# h-bridge_mosfets_ver_4.net
KiCad netlist of a schematic drawn in EAGLE
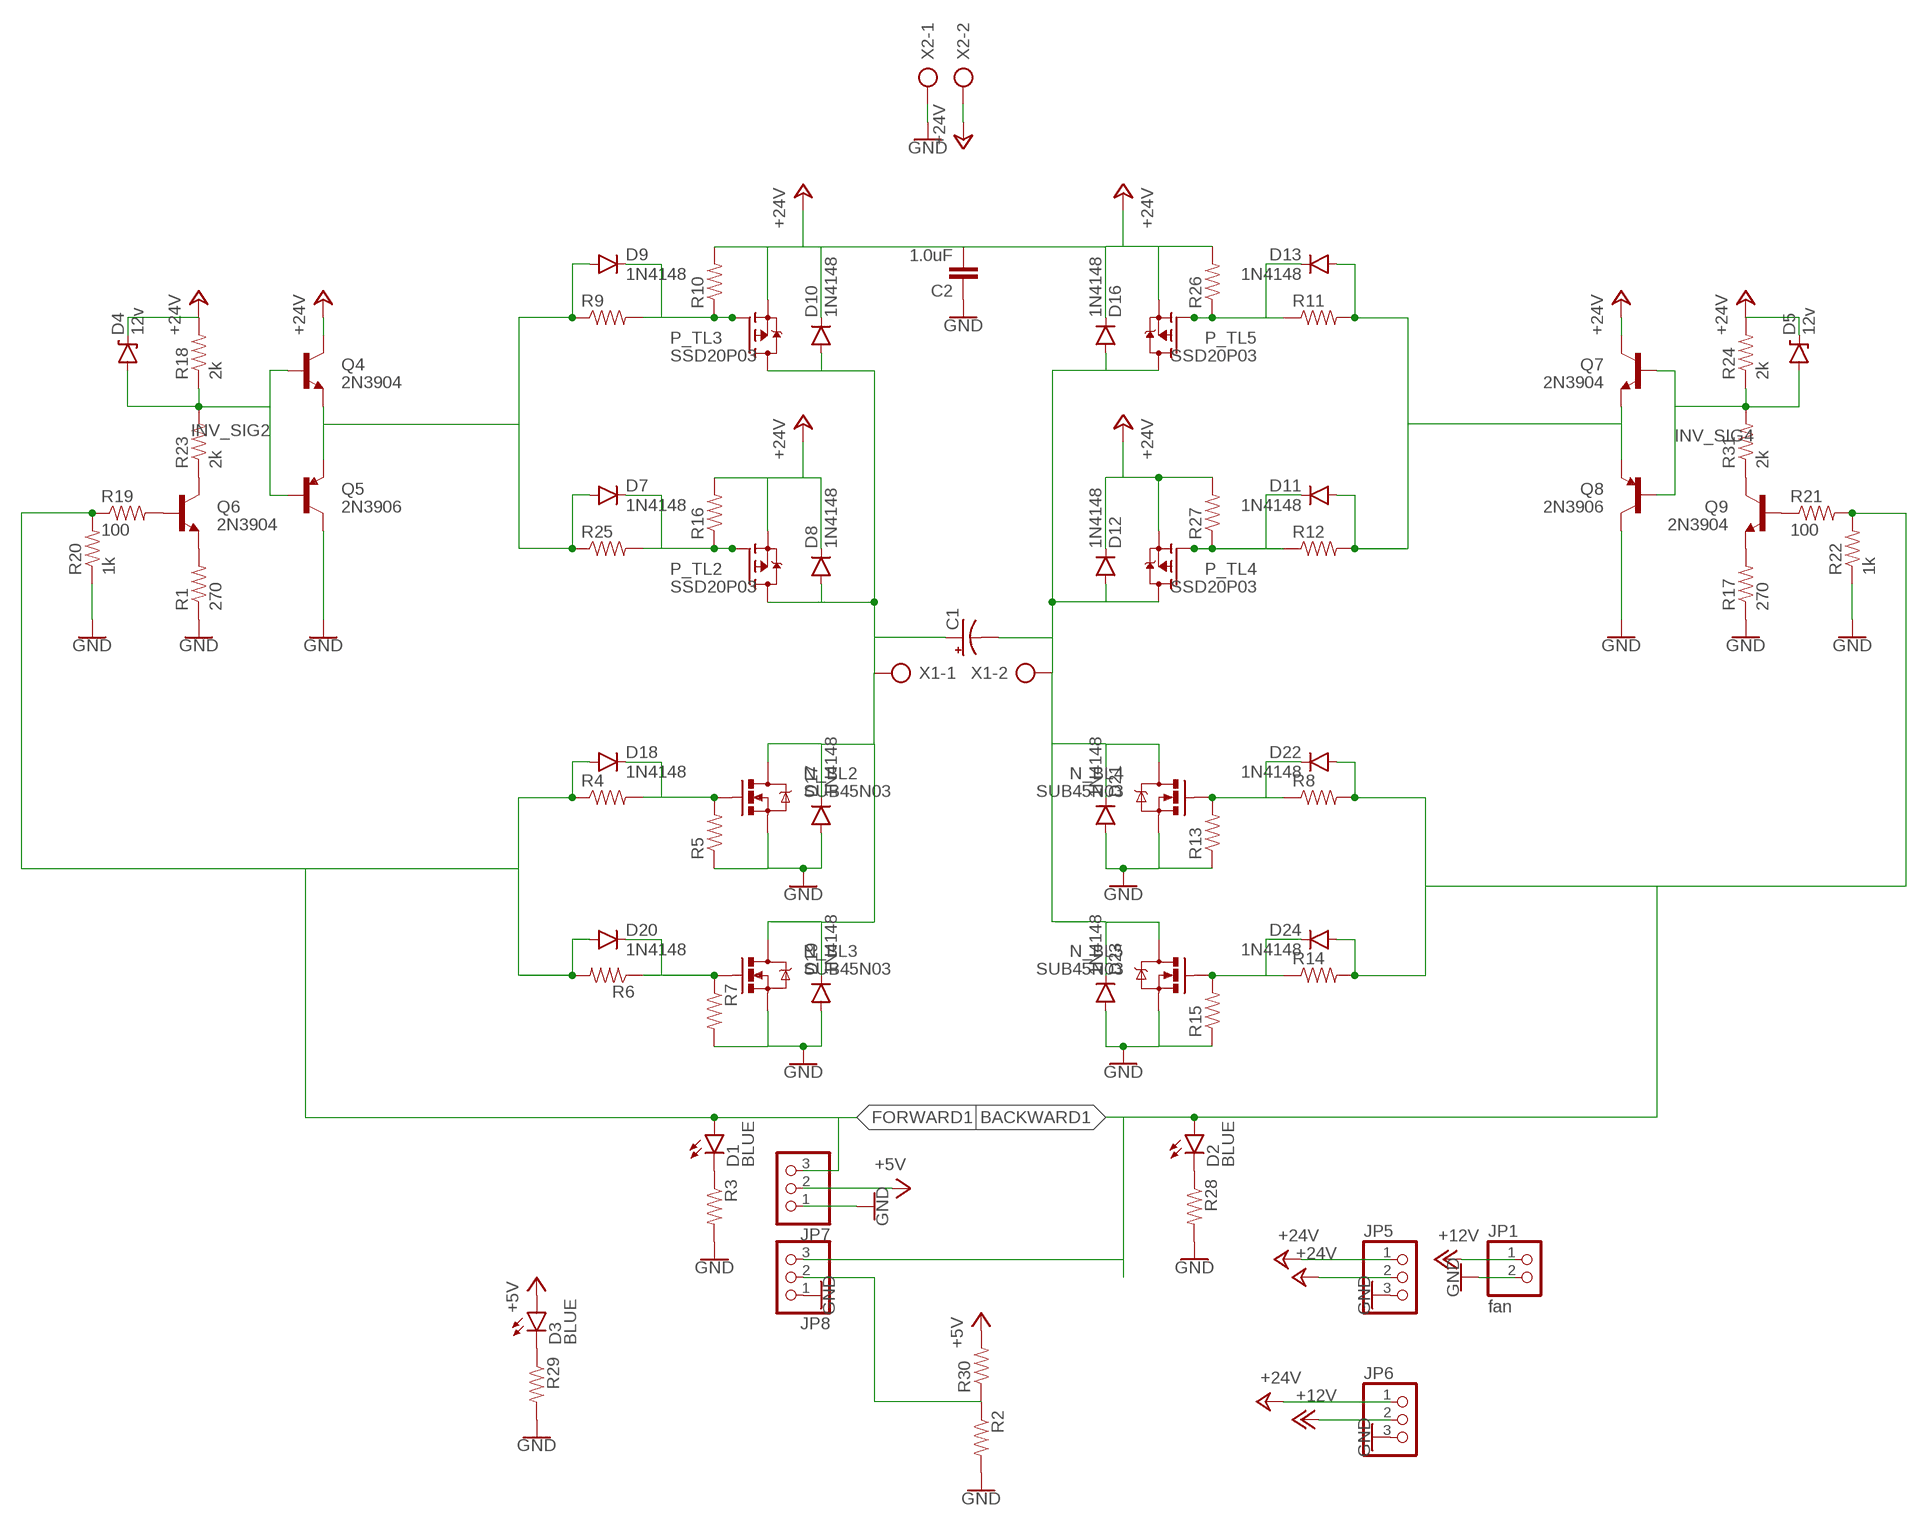
[diagram p0: schematic, sheet 1]

(export (version "E")
  (design (tool "Eeschema 10.0.6"))
  (components
    (comp (ref "C1")
      (value "1000UF-25V(PTH)")
      (footprint "eagle-import:CPOL-RADIAL-1000UF-25V")
      (libsource (lib "eagle-import") (part "1000UF-25V(PTH)"))
    )
    (comp (ref "C2")
      (value "1.0uF")
      (footprint "eagle-import:1206")
      (libsource (lib "eagle-import") (part "1.0UF50V10%(1206)"))
    )
    (comp (ref "D1")
      (value "BLUE")
      (footprint "eagle-import:LED-1206")
      (libsource (lib "eagle-import") (part "LED-BLUE1206"))
    )
    (comp (ref "D2")
      (value "BLUE")
      (footprint "eagle-import:LED-1206")
      (libsource (lib "eagle-import") (part "LED-BLUE1206"))
    )
    (comp (ref "D3")
      (value "BLUE")
      (footprint "eagle-import:LED-1206")
      (libsource (lib "eagle-import") (part "LED-BLUE1206"))
    )
    (comp (ref "D4")
      (value "12v")
      (footprint "eagle-import:SMB-DIODE")
      (libsource (lib "eagle-import") (part "DIODE-ZENERSMB"))
    )
    (comp (ref "D5")
      (value "12v")
      (footprint "eagle-import:SMB-DIODE")
      (libsource (lib "eagle-import") (part "DIODE-ZENERSMB"))
    )
    (comp (ref "D7")
      (value "1N4148")
      (footprint "eagle-import:SOD-123")
      (libsource (lib "eagle-import") (part "DIODESOD123"))
    )
    (comp (ref "D8")
      (value "1N4148")
      (footprint "eagle-import:SOD-123")
      (libsource (lib "eagle-import") (part "DIODESOD123"))
    )
    (comp (ref "D9")
      (value "1N4148")
      (footprint "eagle-import:SOD-123")
      (libsource (lib "eagle-import") (part "DIODESOD123"))
    )
    (comp (ref "D10")
      (value "1N4148")
      (footprint "eagle-import:SOD-123")
      (libsource (lib "eagle-import") (part "DIODESOD123"))
    )
    (comp (ref "D11")
      (value "1N4148")
      (footprint "eagle-import:SOD-123")
      (libsource (lib "eagle-import") (part "DIODESOD123"))
    )
    (comp (ref "D12")
      (value "1N4148")
      (footprint "eagle-import:SOD-123")
      (libsource (lib "eagle-import") (part "DIODESOD123"))
    )
    (comp (ref "D13")
      (value "1N4148")
      (footprint "eagle-import:SOD-123")
      (libsource (lib "eagle-import") (part "DIODESOD123"))
    )
    (comp (ref "D16")
      (value "1N4148")
      (footprint "eagle-import:SOD-123")
      (libsource (lib "eagle-import") (part "DIODESOD123"))
    )
    (comp (ref "D17")
      (value "1N4148")
      (footprint "eagle-import:SOD-123")
      (libsource (lib "eagle-import") (part "DIODESOD123"))
    )
    (comp (ref "D18")
      (value "1N4148")
      (footprint "eagle-import:SOD-123")
      (libsource (lib "eagle-import") (part "DIODESOD123"))
    )
    (comp (ref "D19")
      (value "1N4148")
      (footprint "eagle-import:SOD-123")
      (libsource (lib "eagle-import") (part "DIODESOD123"))
    )
    (comp (ref "D20")
      (value "1N4148")
      (footprint "eagle-import:SOD-123")
      (libsource (lib "eagle-import") (part "DIODESOD123"))
    )
    (comp (ref "D21")
      (value "1N4148")
      (footprint "eagle-import:SOD-123")
      (libsource (lib "eagle-import") (part "DIODESOD123"))
    )
    (comp (ref "D22")
      (value "1N4148")
      (footprint "eagle-import:SOD-123")
      (libsource (lib "eagle-import") (part "DIODESOD123"))
    )
    (comp (ref "D23")
      (value "1N4148")
      (footprint "eagle-import:SOD-123")
      (libsource (lib "eagle-import") (part "DIODESOD123"))
    )
    (comp (ref "D24")
      (value "1N4148")
      (footprint "eagle-import:SOD-123")
      (libsource (lib "eagle-import") (part "DIODESOD123"))
    )
    (comp (ref "JP1")
      (value "fan")
      (footprint "eagle-import:1X02")
      (libsource (lib "eagle-import") (part "PINHD-1X2"))
    )
    (comp (ref "JP5")
      (value "PINHD-1X3")
      (footprint "eagle-import:1X03")
      (libsource (lib "eagle-import") (part "PINHD-1X3"))
    )
    (comp (ref "JP6")
      (value "PINHD-1X3")
      (footprint "eagle-import:1X03")
      (libsource (lib "eagle-import") (part "PINHD-1X3"))
    )
    (comp (ref "JP7")
      (value "PINHD-1X3")
      (footprint "eagle-import:1X03")
      (libsource (lib "eagle-import") (part "PINHD-1X3"))
    )
    (comp (ref "JP8")
      (value "PINHD-1X3")
      (footprint "eagle-import:1X03")
      (libsource (lib "eagle-import") (part "PINHD-1X3"))
    )
    (comp (ref "N_BL2")
      (value "SUB45N03")
      (footprint "eagle-import:TO-263_D2PAK")
      (libsource (lib "eagle-import") (part "MOSFET-NCHANNELPSMN7R0"))
    )
    (comp (ref "N_BL3")
      (value "SUB45N03")
      (footprint "eagle-import:TO-263_D2PAK")
      (libsource (lib "eagle-import") (part "MOSFET-NCHANNELPSMN7R0"))
    )
    (comp (ref "N_BL4")
      (value "SUB45N03")
      (footprint "eagle-import:TO-263_D2PAK")
      (libsource (lib "eagle-import") (part "MOSFET-NCHANNELPSMN7R0"))
    )
    (comp (ref "N_BL5")
      (value "SUB45N03")
      (footprint "eagle-import:TO-263_D2PAK")
      (libsource (lib "eagle-import") (part "MOSFET-NCHANNELPSMN7R0"))
    )
    (comp (ref "P_TL2")
      (value "SSD20P03")
      (footprint "eagle-import:TO252")
      (libsource (lib "eagle-import") (part "FDD4141TO252"))
    )
    (comp (ref "P_TL3")
      (value "SSD20P03")
      (footprint "eagle-import:TO252")
      (libsource (lib "eagle-import") (part "FDD4141TO252"))
    )
    (comp (ref "P_TL4")
      (value "SSD20P03")
      (footprint "eagle-import:TO252")
      (libsource (lib "eagle-import") (part "FDD4141TO252"))
    )
    (comp (ref "P_TL5")
      (value "SSD20P03")
      (footprint "eagle-import:TO252")
      (libsource (lib "eagle-import") (part "FDD4141TO252"))
    )
    (comp (ref "Q4")
      (value "2N3904")
      (footprint "eagle-import:SOT23-3")
      (libsource (lib "eagle-import") (part "TRANSISTOR_NPNMMBT5088"))
    )
    (comp (ref "Q5")
      (value "2N3906")
      (footprint "eagle-import:SOT23-3")
      (libsource (lib "eagle-import") (part "TRANSISTOR_PNPPMBT3906"))
    )
    (comp (ref "Q6")
      (value "2N3904")
      (footprint "eagle-import:SOT23-3")
      (libsource (lib "eagle-import") (part "TRANSISTOR_NPNMMBT5088"))
    )
    (comp (ref "Q7")
      (value "2N3904")
      (footprint "eagle-import:SOT23-3")
      (libsource (lib "eagle-import") (part "TRANSISTOR_NPNMMBT5088"))
    )
    (comp (ref "Q8")
      (value "2N3906")
      (footprint "eagle-import:SOT23-3")
      (libsource (lib "eagle-import") (part "TRANSISTOR_PNPPMBT3906"))
    )
    (comp (ref "Q9")
      (value "2N3904")
      (footprint "eagle-import:SOT23-3")
      (libsource (lib "eagle-import") (part "TRANSISTOR_NPNMMBT5088"))
    )
    (comp (ref "R1")
      (value "270")
      (footprint "eagle-import:0805")
      (libsource (lib "eagle-import") (part "0.3OHM-1/8W-1%(0805)"))
    )
    (comp (ref "R2")
      (value "0.3OHM-1/8W-1%(0805)")
      (footprint "eagle-import:0805")
      (libsource (lib "eagle-import") (part "0.3OHM-1/8W-1%(0805)"))
    )
    (comp (ref "R3")
      (value "0.3OHM-1/8W-1%(0805)")
      (footprint "eagle-import:0805")
      (libsource (lib "eagle-import") (part "0.3OHM-1/8W-1%(0805)"))
    )
    (comp (ref "R4")
      (value "0.3OHM-1/8W-1%(0805)")
      (footprint "eagle-import:0805")
      (libsource (lib "eagle-import") (part "0.3OHM-1/8W-1%(0805)"))
    )
    (comp (ref "R5")
      (value "0.3OHM-1/8W-1%(0805)")
      (footprint "eagle-import:0805")
      (libsource (lib "eagle-import") (part "0.3OHM-1/8W-1%(0805)"))
    )
    (comp (ref "R6")
      (value "0.3OHM-1/8W-1%(0805)")
      (footprint "eagle-import:0805")
      (libsource (lib "eagle-import") (part "0.3OHM-1/8W-1%(0805)"))
    )
    (comp (ref "R7")
      (value "0.3OHM-1/8W-1%(0805)")
      (footprint "eagle-import:0805")
      (libsource (lib "eagle-import") (part "0.3OHM-1/8W-1%(0805)"))
    )
    (comp (ref "R8")
      (value "0.3OHM-1/8W-1%(0805)")
      (footprint "eagle-import:0805")
      (libsource (lib "eagle-import") (part "0.3OHM-1/8W-1%(0805)"))
    )
    (comp (ref "R9")
      (value "0.3OHM-1/8W-1%(0805)")
      (footprint "eagle-import:0805")
      (libsource (lib "eagle-import") (part "0.3OHM-1/8W-1%(0805)"))
    )
    (comp (ref "R10")
      (value "0.3OHM-1/8W-1%(0805)")
      (footprint "eagle-import:0805")
      (libsource (lib "eagle-import") (part "0.3OHM-1/8W-1%(0805)"))
    )
    (comp (ref "R11")
      (value "0.3OHM-1/8W-1%(0805)")
      (footprint "eagle-import:0805")
      (libsource (lib "eagle-import") (part "0.3OHM-1/8W-1%(0805)"))
    )
    (comp (ref "R12")
      (value "0.3OHM-1/8W-1%(0805)")
      (footprint "eagle-import:0805")
      (libsource (lib "eagle-import") (part "0.3OHM-1/8W-1%(0805)"))
    )
    (comp (ref "R13")
      (value "0.3OHM-1/8W-1%(0805)")
      (footprint "eagle-import:0805")
      (libsource (lib "eagle-import") (part "0.3OHM-1/8W-1%(0805)"))
    )
    (comp (ref "R14")
      (value "0.3OHM-1/8W-1%(0805)")
      (footprint "eagle-import:0805")
      (libsource (lib "eagle-import") (part "0.3OHM-1/8W-1%(0805)"))
    )
    (comp (ref "R15")
      (value "0.3OHM-1/8W-1%(0805)")
      (footprint "eagle-import:0805")
      (libsource (lib "eagle-import") (part "0.3OHM-1/8W-1%(0805)"))
    )
    (comp (ref "R16")
      (value "0.3OHM-1/8W-1%(0805)")
      (footprint "eagle-import:0805")
      (libsource (lib "eagle-import") (part "0.3OHM-1/8W-1%(0805)"))
    )
    (comp (ref "R17")
      (value "270")
      (footprint "eagle-import:0805")
      (libsource (lib "eagle-import") (part "0.3OHM-1/8W-1%(0805)"))
    )
    (comp (ref "R18")
      (value "2k")
      (footprint "eagle-import:0805")
      (libsource (lib "eagle-import") (part "0.3OHM-1/8W-1%(0805)"))
    )
    (comp (ref "R19")
      (value "100")
      (footprint "eagle-import:0805")
      (libsource (lib "eagle-import") (part "0.3OHM-1/8W-1%(0805)"))
    )
    (comp (ref "R20")
      (value "1k")
      (footprint "eagle-import:0805")
      (libsource (lib "eagle-import") (part "0.3OHM-1/8W-1%(0805)"))
    )
    (comp (ref "R21")
      (value "100")
      (footprint "eagle-import:0805")
      (libsource (lib "eagle-import") (part "0.3OHM-1/8W-1%(0805)"))
    )
    (comp (ref "R22")
      (value "1k")
      (footprint "eagle-import:0805")
      (libsource (lib "eagle-import") (part "0.3OHM-1/8W-1%(0805)"))
    )
    (comp (ref "R23")
      (value "2k")
      (footprint "eagle-import:0805")
      (libsource (lib "eagle-import") (part "0.3OHM-1/8W-1%(0805)"))
    )
    (comp (ref "R24")
      (value "2k")
      (footprint "eagle-import:0805")
      (libsource (lib "eagle-import") (part "0.3OHM-1/8W-1%(0805)"))
    )
    (comp (ref "R25")
      (value "0.3OHM-1/8W-1%(0805)")
      (footprint "eagle-import:0805")
      (libsource (lib "eagle-import") (part "0.3OHM-1/8W-1%(0805)"))
    )
    (comp (ref "R26")
      (value "0.3OHM-1/8W-1%(0805)")
      (footprint "eagle-import:0805")
      (libsource (lib "eagle-import") (part "0.3OHM-1/8W-1%(0805)"))
    )
    (comp (ref "R27")
      (value "0.3OHM-1/8W-1%(0805)")
      (footprint "eagle-import:0805")
      (libsource (lib "eagle-import") (part "0.3OHM-1/8W-1%(0805)"))
    )
    (comp (ref "R28")
      (value "0.3OHM-1/8W-1%(0805)")
      (footprint "eagle-import:0805")
      (libsource (lib "eagle-import") (part "0.3OHM-1/8W-1%(0805)"))
    )
    (comp (ref "R29")
      (value "0.3OHM-1/8W-1%(0805)")
      (footprint "eagle-import:0805")
      (libsource (lib "eagle-import") (part "0.3OHM-1/8W-1%(0805)"))
    )
    (comp (ref "R30")
      (value "RESISTORPTH-1/4W-VERT-KIT")
      (footprint "eagle-import:AXIAL-0.1EZ")
      (libsource (lib "eagle-import") (part "RESISTORPTH-1/4W-VERT-KIT"))
    )
    (comp (ref "R31")
      (value "2k")
      (footprint "eagle-import:0805")
      (libsource (lib "eagle-import") (part "0.3OHM-1/8W-1%(0805)"))
    )
    (comp (ref "X1")
      (value "AK300/2")
      (footprint "eagle-import:AK300_2")
      (libsource (lib "eagle-import") (part "AK300/2"))
    )
    (comp (ref "X2")
      (value "AK300/2")
      (footprint "eagle-import:AK300_2")
      (libsource (lib "eagle-import") (part "AK300/2"))
    )
  )
  (nets
    (net (code "1") (name "+5V") (class "Default")
      (node (ref "D3") (pin "A") (pinfunction "A_A") (pintype "passive"))
      (node (ref "JP7") (pin "2") (pinfunction "2_2") (pintype "passive"))
      (node (ref "R30") (pin "P$2") (pinfunction "2_P$2") (pintype "passive"))
    )
    (net (code "2") (name "+12V") (class "Default")
      (node (ref "JP1") (pin "1") (pinfunction "1_1") (pintype "passive"))
      (node (ref "JP6") (pin "2") (pinfunction "2_2") (pintype "passive"))
    )
    (net (code "3") (name "+24V") (class "Default")
      (node (ref "C2") (pin "2") (pinfunction "2_2") (pintype "passive"))
      (node (ref "D10") (pin "C") (pinfunction "C_C") (pintype "passive"))
      (node (ref "D12") (pin "C") (pinfunction "C_C") (pintype "passive"))
      (node (ref "D16") (pin "C") (pinfunction "C_C") (pintype "passive"))
      (node (ref "D4") (pin "C") (pinfunction "C_C") (pintype "passive"))
      (node (ref "D5") (pin "C") (pinfunction "C_C") (pintype "passive"))
      (node (ref "D8") (pin "C") (pinfunction "C_C") (pintype "passive"))
      (node (ref "JP5") (pin "1") (pinfunction "1_1") (pintype "passive"))
      (node (ref "JP5") (pin "2") (pinfunction "2_2") (pintype "passive"))
      (node (ref "JP6") (pin "1") (pinfunction "1_1") (pintype "passive"))
      (node (ref "P_TL2") (pin "2") (pinfunction "S_2") (pintype "passive"))
      (node (ref "P_TL3") (pin "2") (pinfunction "S_2") (pintype "passive"))
      (node (ref "P_TL4") (pin "2") (pinfunction "S_2") (pintype "passive"))
      (node (ref "P_TL5") (pin "2") (pinfunction "S_2") (pintype "passive"))
      (node (ref "Q4") (pin "3") (pinfunction "C_3") (pintype "passive"))
      (node (ref "Q7") (pin "3") (pinfunction "C_3") (pintype "passive"))
      (node (ref "R10") (pin "2") (pinfunction "2_2") (pintype "passive"))
      (node (ref "R16") (pin "2") (pinfunction "2_2") (pintype "passive"))
      (node (ref "R18") (pin "2") (pinfunction "2_2") (pintype "passive"))
      (node (ref "R24") (pin "2") (pinfunction "2_2") (pintype "passive"))
      (node (ref "R26") (pin "2") (pinfunction "2_2") (pintype "passive"))
      (node (ref "R27") (pin "2") (pinfunction "2_2") (pintype "passive"))
      (node (ref "X2") (pin "2") (pinfunction "KL_2") (pintype "passive"))
    )
    (net (code "4") (name "/INV_SIG2") (class "Default")
      (node (ref "D4") (pin "A") (pinfunction "A_A") (pintype "passive"))
      (node (ref "Q4") (pin "1") (pinfunction "B_1") (pintype "passive"))
      (node (ref "Q5") (pin "1") (pinfunction "B_1") (pintype "passive"))
      (node (ref "R18") (pin "1") (pinfunction "1_1") (pintype "passive"))
      (node (ref "R23") (pin "2") (pinfunction "2_2") (pintype "passive"))
    )
    (net (code "5") (name "/INV_SIG4") (class "Default")
      (node (ref "D5") (pin "A") (pinfunction "A_A") (pintype "passive"))
      (node (ref "Q7") (pin "1") (pinfunction "B_1") (pintype "passive"))
      (node (ref "Q8") (pin "1") (pinfunction "B_1") (pintype "passive"))
      (node (ref "R24") (pin "1") (pinfunction "1_1") (pintype "passive"))
      (node (ref "R31") (pin "2") (pinfunction "2_2") (pintype "passive"))
    )
    (net (code "6") (name "BACKWARD1") (class "Default")
      (node (ref "D2") (pin "A") (pinfunction "A_A") (pintype "passive"))
      (node (ref "D22") (pin "A") (pinfunction "A_A") (pintype "passive"))
      (node (ref "D24") (pin "A") (pinfunction "A_A") (pintype "passive"))
      (node (ref "JP8") (pin "3") (pinfunction "3_3") (pintype "passive"))
      (node (ref "R14") (pin "2") (pinfunction "2_2") (pintype "passive"))
      (node (ref "R21") (pin "2") (pinfunction "2_2") (pintype "passive"))
      (node (ref "R22") (pin "2") (pinfunction "2_2") (pintype "passive"))
      (node (ref "R8") (pin "2") (pinfunction "2_2") (pintype "passive"))
    )
    (net (code "7") (name "FORWARD1") (class "Default")
      (node (ref "D1") (pin "A") (pinfunction "A_A") (pintype "passive"))
      (node (ref "D18") (pin "A") (pinfunction "A_A") (pintype "passive"))
      (node (ref "D20") (pin "A") (pinfunction "A_A") (pintype "passive"))
      (node (ref "JP7") (pin "3") (pinfunction "3_3") (pintype "passive"))
      (node (ref "R19") (pin "1") (pinfunction "1_1") (pintype "passive"))
      (node (ref "R20") (pin "2") (pinfunction "2_2") (pintype "passive"))
      (node (ref "R4") (pin "1") (pinfunction "1_1") (pintype "passive"))
      (node (ref "R6") (pin "2") (pinfunction "2_2") (pintype "passive"))
    )
    (net (code "8") (name "GND") (class "Default")
      (node (ref "C2") (pin "1") (pinfunction "1_1") (pintype "passive"))
      (node (ref "D17") (pin "A") (pinfunction "A_A") (pintype "passive"))
      (node (ref "D19") (pin "A") (pinfunction "A_A") (pintype "passive"))
      (node (ref "D21") (pin "A") (pinfunction "A_A") (pintype "passive"))
      (node (ref "D23") (pin "A") (pinfunction "A_A") (pintype "passive"))
      (node (ref "JP1") (pin "2") (pinfunction "2_2") (pintype "passive"))
      (node (ref "JP5") (pin "3") (pinfunction "3_3") (pintype "passive"))
      (node (ref "JP6") (pin "3") (pinfunction "3_3") (pintype "passive"))
      (node (ref "JP7") (pin "1") (pinfunction "1_1") (pintype "passive"))
      (node (ref "JP8") (pin "1") (pinfunction "1_1") (pintype "passive"))
      (node (ref "N_BL2") (pin "3") (pinfunction "S_3") (pintype "passive"))
      (node (ref "N_BL3") (pin "3") (pinfunction "S_3") (pintype "passive"))
      (node (ref "N_BL4") (pin "3") (pinfunction "S_3") (pintype "passive"))
      (node (ref "N_BL5") (pin "3") (pinfunction "S_3") (pintype "passive"))
      (node (ref "Q5") (pin "3") (pinfunction "C_3") (pintype "passive"))
      (node (ref "Q8") (pin "3") (pinfunction "C_3") (pintype "passive"))
      (node (ref "R1") (pin "1") (pinfunction "1_1") (pintype "passive"))
      (node (ref "R13") (pin "1") (pinfunction "1_1") (pintype "passive"))
      (node (ref "R15") (pin "1") (pinfunction "1_1") (pintype "passive"))
      (node (ref "R17") (pin "1") (pinfunction "1_1") (pintype "passive"))
      (node (ref "R2") (pin "2") (pinfunction "2_2") (pintype "passive"))
      (node (ref "R20") (pin "1") (pinfunction "1_1") (pintype "passive"))
      (node (ref "R22") (pin "1") (pinfunction "1_1") (pintype "passive"))
      (node (ref "R28") (pin "2") (pinfunction "2_2") (pintype "passive"))
      (node (ref "R29") (pin "2") (pinfunction "2_2") (pintype "passive"))
      (node (ref "R3") (pin "2") (pinfunction "2_2") (pintype "passive"))
      (node (ref "R5") (pin "1") (pinfunction "1_1") (pintype "passive"))
      (node (ref "R7") (pin "2") (pinfunction "2_2") (pintype "passive"))
      (node (ref "X2") (pin "1") (pinfunction "KL_1") (pintype "passive"))
    )
    (net (code "9") (name "Net-(D1-PadC)") (class "Default")
      (node (ref "D1") (pin "C") (pinfunction "C_C") (pintype "passive"))
      (node (ref "R3") (pin "1") (pinfunction "1_1") (pintype "passive"))
    )
    (net (code "10") (name "Net-(D2-PadC)") (class "Default")
      (node (ref "D2") (pin "C") (pinfunction "C_C") (pintype "passive"))
      (node (ref "R28") (pin "1") (pinfunction "1_1") (pintype "passive"))
    )
    (net (code "11") (name "Net-(D3-PadC)") (class "Default")
      (node (ref "D3") (pin "C") (pinfunction "C_C") (pintype "passive"))
      (node (ref "R29") (pin "1") (pinfunction "1_1") (pintype "passive"))
    )
    (net (code "12") (name "Net-(N_BL2-D)") (class "Default")
      (node (ref "C1") (pin "+") (pinfunction "+_+") (pintype "passive"))
      (node (ref "D10") (pin "A") (pinfunction "A_A") (pintype "passive"))
      (node (ref "D17") (pin "C") (pinfunction "C_C") (pintype "passive"))
      (node (ref "D19") (pin "C") (pinfunction "C_C") (pintype "passive"))
      (node (ref "D8") (pin "A") (pinfunction "A_A") (pintype "passive"))
      (node (ref "N_BL2") (pin "2") (pinfunction "D_2") (pintype "passive"))
      (node (ref "N_BL3") (pin "2") (pinfunction "D_2") (pintype "passive"))
      (node (ref "P_TL2") (pin "3") (pinfunction "D_3") (pintype "passive"))
      (node (ref "P_TL3") (pin "3") (pinfunction "D_3") (pintype "passive"))
      (node (ref "X1") (pin "1") (pinfunction "KL_1") (pintype "passive"))
    )
    (net (code "13") (name "Net-(N_BL2-G)") (class "Default")
      (node (ref "D18") (pin "C") (pinfunction "C_C") (pintype "passive"))
      (node (ref "N_BL2") (pin "1") (pinfunction "G_1") (pintype "passive"))
      (node (ref "R4") (pin "2") (pinfunction "2_2") (pintype "passive"))
      (node (ref "R5") (pin "2") (pinfunction "2_2") (pintype "passive"))
    )
    (net (code "14") (name "Net-(N_BL3-G)") (class "Default")
      (node (ref "D20") (pin "C") (pinfunction "C_C") (pintype "passive"))
      (node (ref "N_BL3") (pin "1") (pinfunction "G_1") (pintype "passive"))
      (node (ref "R6") (pin "1") (pinfunction "1_1") (pintype "passive"))
      (node (ref "R7") (pin "1") (pinfunction "1_1") (pintype "passive"))
    )
    (net (code "15") (name "Net-(N_BL4-D)") (class "Default")
      (node (ref "C1") (pin "-") (pinfunction "-_-") (pintype "passive"))
      (node (ref "D12") (pin "A") (pinfunction "A_A") (pintype "passive"))
      (node (ref "D16") (pin "A") (pinfunction "A_A") (pintype "passive"))
      (node (ref "D21") (pin "C") (pinfunction "C_C") (pintype "passive"))
      (node (ref "D23") (pin "C") (pinfunction "C_C") (pintype "passive"))
      (node (ref "N_BL4") (pin "2") (pinfunction "D_2") (pintype "passive"))
      (node (ref "N_BL5") (pin "2") (pinfunction "D_2") (pintype "passive"))
      (node (ref "P_TL4") (pin "3") (pinfunction "D_3") (pintype "passive"))
      (node (ref "P_TL5") (pin "3") (pinfunction "D_3") (pintype "passive"))
      (node (ref "X1") (pin "2") (pinfunction "KL_2") (pintype "passive"))
    )
    (net (code "16") (name "Net-(N_BL4-G)") (class "Default")
      (node (ref "D22") (pin "C") (pinfunction "C_C") (pintype "passive"))
      (node (ref "N_BL4") (pin "1") (pinfunction "G_1") (pintype "passive"))
      (node (ref "R13") (pin "2") (pinfunction "2_2") (pintype "passive"))
      (node (ref "R8") (pin "1") (pinfunction "1_1") (pintype "passive"))
    )
    (net (code "17") (name "Net-(N_BL5-G)") (class "Default")
      (node (ref "D24") (pin "C") (pinfunction "C_C") (pintype "passive"))
      (node (ref "N_BL5") (pin "1") (pinfunction "G_1") (pintype "passive"))
      (node (ref "R14") (pin "1") (pinfunction "1_1") (pintype "passive"))
      (node (ref "R15") (pin "2") (pinfunction "2_2") (pintype "passive"))
    )
    (net (code "18") (name "Net-(P_TL2-G)") (class "Default")
      (node (ref "D7") (pin "C") (pinfunction "C_C") (pintype "passive"))
      (node (ref "P_TL2") (pin "1") (pinfunction "G_1") (pintype "passive"))
      (node (ref "R16") (pin "1") (pinfunction "1_1") (pintype "passive"))
      (node (ref "R25") (pin "2") (pinfunction "2_2") (pintype "passive"))
    )
    (net (code "19") (name "Net-(P_TL3-G)") (class "Default")
      (node (ref "D9") (pin "C") (pinfunction "C_C") (pintype "passive"))
      (node (ref "P_TL3") (pin "1") (pinfunction "G_1") (pintype "passive"))
      (node (ref "R10") (pin "1") (pinfunction "1_1") (pintype "passive"))
      (node (ref "R9") (pin "2") (pinfunction "2_2") (pintype "passive"))
    )
    (net (code "20") (name "Net-(P_TL4-G)") (class "Default")
      (node (ref "D11") (pin "C") (pinfunction "C_C") (pintype "passive"))
      (node (ref "P_TL4") (pin "1") (pinfunction "G_1") (pintype "passive"))
      (node (ref "R12") (pin "1") (pinfunction "1_1") (pintype "passive"))
      (node (ref "R27") (pin "1") (pinfunction "1_1") (pintype "passive"))
    )
    (net (code "21") (name "Net-(P_TL5-G)") (class "Default")
      (node (ref "D13") (pin "C") (pinfunction "C_C") (pintype "passive"))
      (node (ref "P_TL5") (pin "1") (pinfunction "G_1") (pintype "passive"))
      (node (ref "R11") (pin "1") (pinfunction "1_1") (pintype "passive"))
      (node (ref "R26") (pin "1") (pinfunction "1_1") (pintype "passive"))
    )
    (net (code "22") (name "Net-(Q4-E)") (class "Default")
      (node (ref "D7") (pin "A") (pinfunction "A_A") (pintype "passive"))
      (node (ref "D9") (pin "A") (pinfunction "A_A") (pintype "passive"))
      (node (ref "Q4") (pin "2") (pinfunction "E_2") (pintype "passive"))
      (node (ref "Q5") (pin "2") (pinfunction "E_2") (pintype "passive"))
      (node (ref "R25") (pin "1") (pinfunction "1_1") (pintype "passive"))
      (node (ref "R9") (pin "1") (pinfunction "1_1") (pintype "passive"))
    )
    (net (code "23") (name "Net-(Q6-B)") (class "Default")
      (node (ref "Q6") (pin "1") (pinfunction "B_1") (pintype "passive"))
      (node (ref "R19") (pin "2") (pinfunction "2_2") (pintype "passive"))
    )
    (net (code "24") (name "Net-(Q6-C)") (class "Default")
      (node (ref "Q6") (pin "3") (pinfunction "C_3") (pintype "passive"))
      (node (ref "R23") (pin "1") (pinfunction "1_1") (pintype "passive"))
    )
    (net (code "25") (name "Net-(Q6-E)") (class "Default")
      (node (ref "Q6") (pin "2") (pinfunction "E_2") (pintype "passive"))
      (node (ref "R1") (pin "2") (pinfunction "2_2") (pintype "passive"))
    )
    (net (code "26") (name "Net-(Q7-E)") (class "Default")
      (node (ref "D11") (pin "A") (pinfunction "A_A") (pintype "passive"))
      (node (ref "D13") (pin "A") (pinfunction "A_A") (pintype "passive"))
      (node (ref "Q7") (pin "2") (pinfunction "E_2") (pintype "passive"))
      (node (ref "Q8") (pin "2") (pinfunction "E_2") (pintype "passive"))
      (node (ref "R11") (pin "2") (pinfunction "2_2") (pintype "passive"))
      (node (ref "R12") (pin "2") (pinfunction "2_2") (pintype "passive"))
    )
    (net (code "27") (name "Net-(Q9-B)") (class "Default")
      (node (ref "Q9") (pin "1") (pinfunction "B_1") (pintype "passive"))
      (node (ref "R21") (pin "1") (pinfunction "1_1") (pintype "passive"))
    )
    (net (code "28") (name "Net-(Q9-C)") (class "Default")
      (node (ref "Q9") (pin "3") (pinfunction "C_3") (pintype "passive"))
      (node (ref "R31") (pin "1") (pinfunction "1_1") (pintype "passive"))
    )
    (net (code "29") (name "Net-(Q9-E)") (class "Default")
      (node (ref "Q9") (pin "2") (pinfunction "E_2") (pintype "passive"))
      (node (ref "R17") (pin "2") (pinfunction "2_2") (pintype "passive"))
    )
    (net (code "30") (name "Net-(R30-1)") (class "Default")
      (node (ref "JP8") (pin "2") (pinfunction "2_2") (pintype "passive"))
      (node (ref "R2") (pin "1") (pinfunction "1_1") (pintype "passive"))
      (node (ref "R30") (pin "P$1") (pinfunction "1_P$1") (pintype "passive"))
    )
  )
)
